# HELIALights2022V1_0Sheet2.net
KiCad netlist of a schematic drawn in Altium Designer
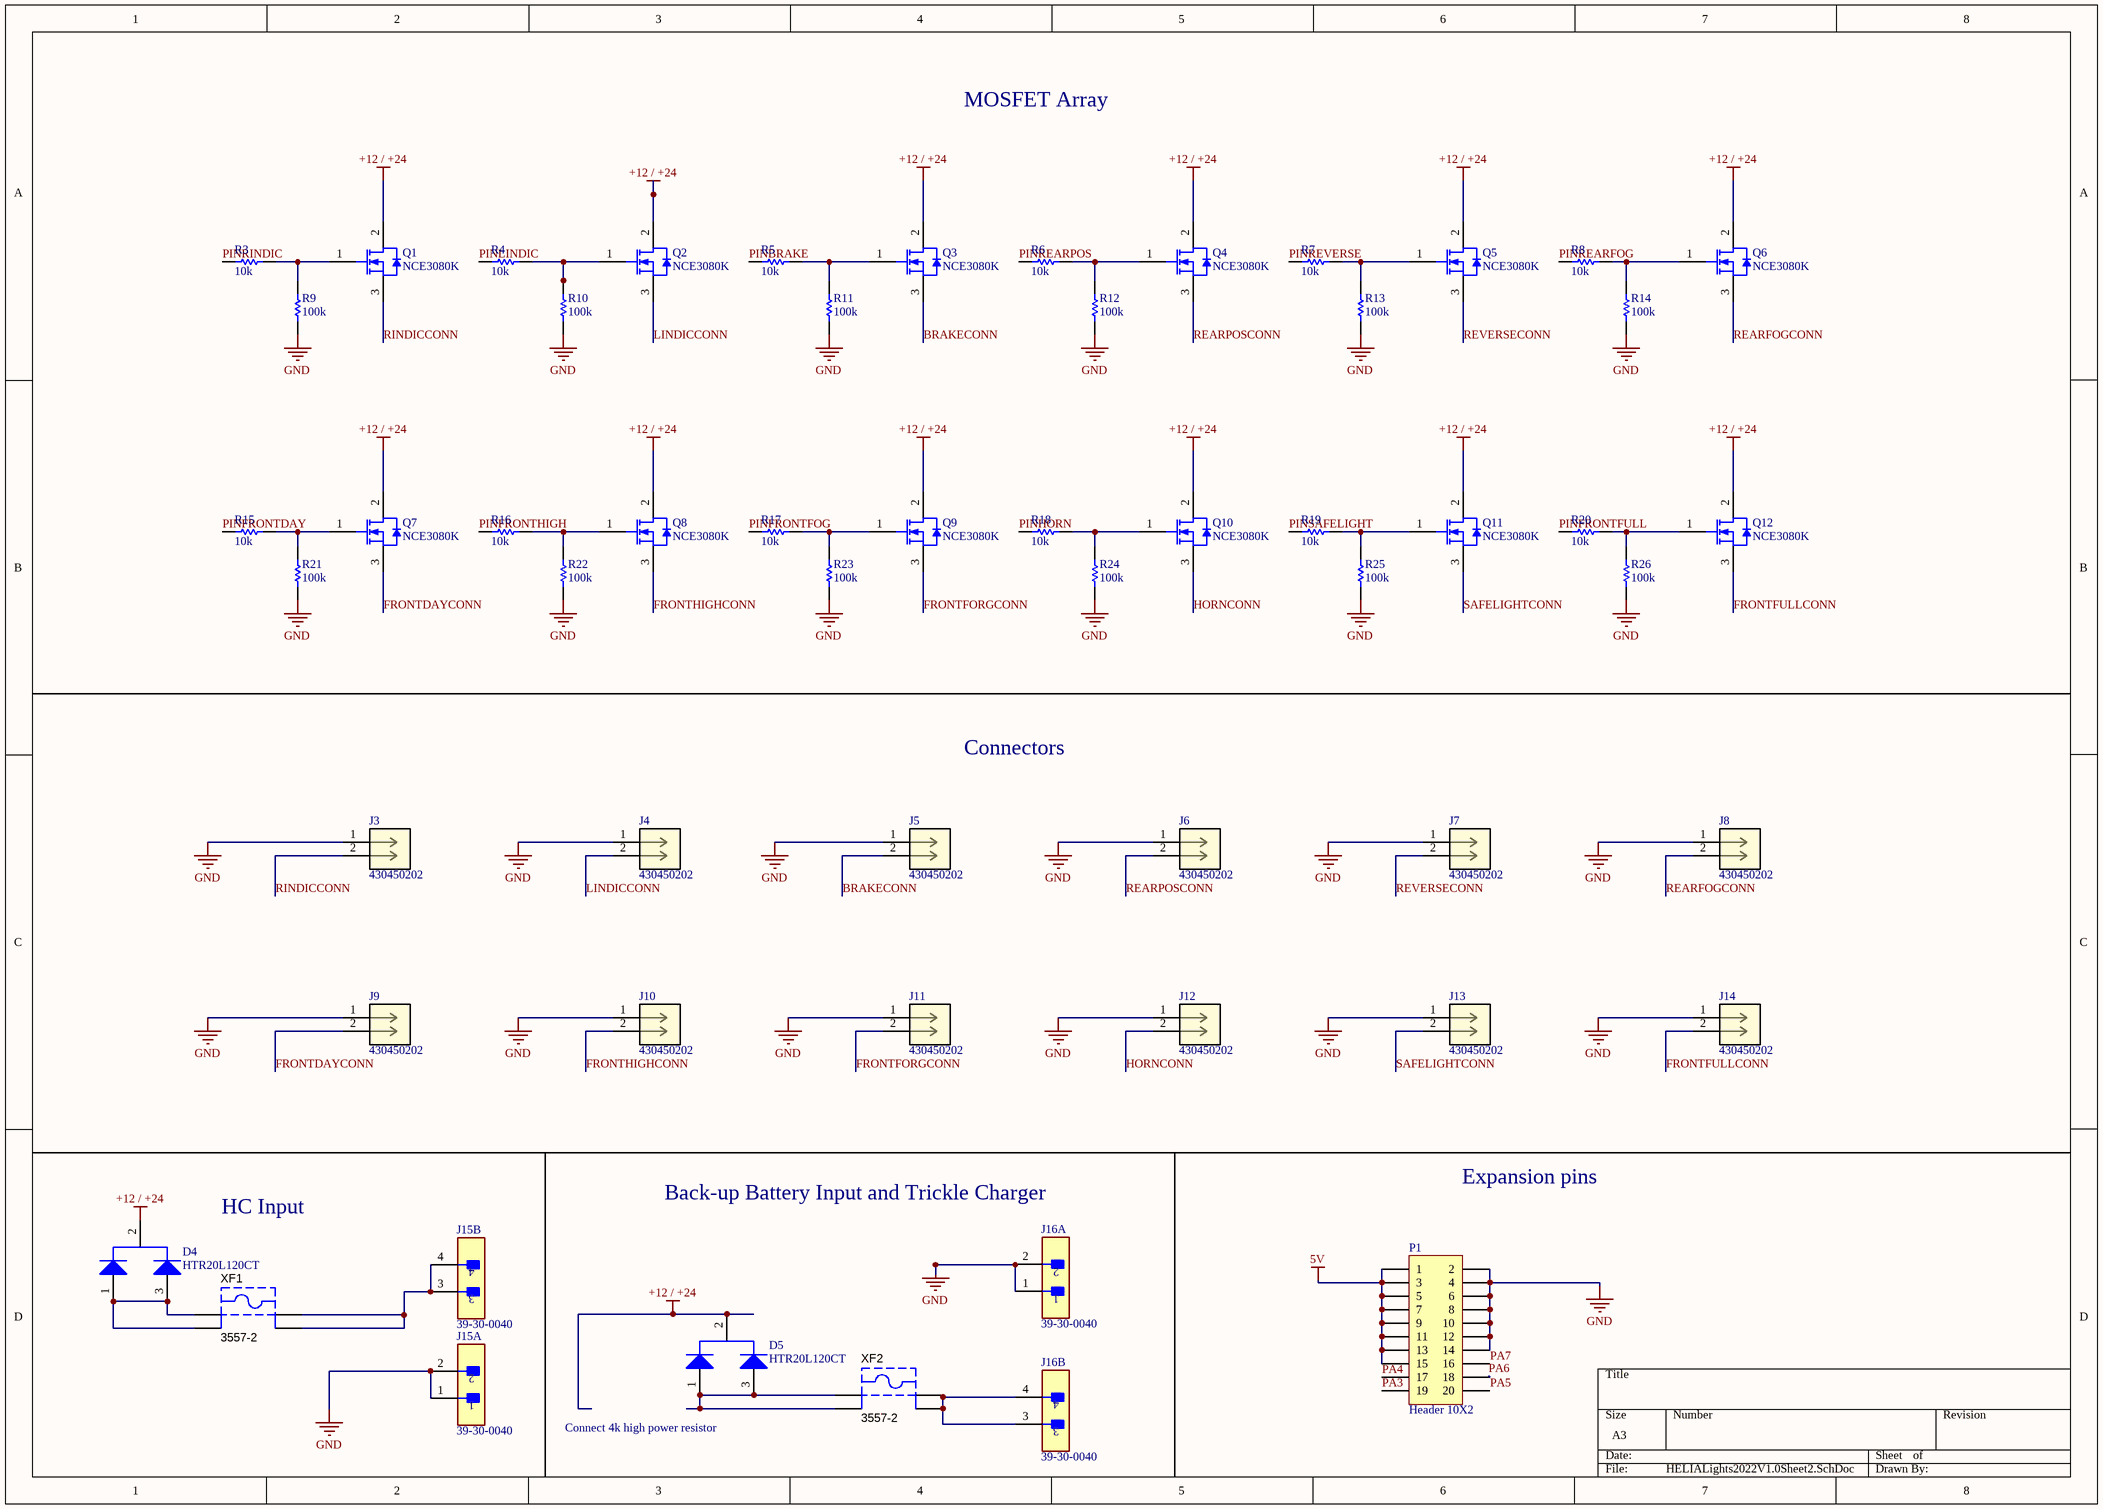
[diagram p0: HELIALights2022V1.0Sheet2.SchDoc]

(export (version "E")
  (design (tool "Eeschema 10.0.6"))
  (components
    (comp (ref "D4")
      (value "HTR20L120CT")
      (footprint "ONSC-TO-220-3-221A-09")
      (description "SWITCHMODE(TM) Power Rectifier, 60 V, 30 A, 3-Pin TO-220, Pb-Free, Tube")
      (fields (field (name "MANUFACTURER") "On Semiconductor") (field (name "PARTNUMBER") "MBR30H60CTG"))
      (libsource (lib "Altium Content Vault") (part "ONSC-D-A1K2A3-3_B"))
    )
    (comp (ref "D5")
      (value "HTR20L120CT")
      (footprint "ONSC-TO-220-3-221A-09")
      (description "SWITCHMODE(TM) Power Rectifier, 60 V, 30 A, 3-Pin TO-220, Pb-Free, Tube")
      (fields (field (name "MANUFACTURER") "On Semiconductor") (field (name "PARTNUMBER") "MBR30H60CTG"))
      (libsource (lib "Altium Content Vault") (part "ONSC-D-A1K2A3-3_B"))
    )
    (comp (ref "J3")
      (value "430450202")
      (footprint "CON_430450202_MOL")
      (description "No Description Available")
      (fields (field (name "COPYRIGHT") "Copyright (C) 2022 Ultra Librarian. All rights reserved."))
      (libsource (lib "430450202") (part "430450202"))
    )
    (comp (ref "J4")
      (value "430450202")
      (footprint "CON_430450202_MOL")
      (description "No Description Available")
      (fields (field (name "COPYRIGHT") "Copyright (C) 2022 Ultra Librarian. All rights reserved."))
      (libsource (lib "430450202") (part "430450202"))
    )
    (comp (ref "J5")
      (value "430450202")
      (footprint "CON_430450202_MOL")
      (description "No Description Available")
      (fields (field (name "COPYRIGHT") "Copyright (C) 2022 Ultra Librarian. All rights reserved."))
      (libsource (lib "430450202") (part "430450202"))
    )
    (comp (ref "J6")
      (value "430450202")
      (footprint "CON_430450202_MOL")
      (description "No Description Available")
      (fields (field (name "COPYRIGHT") "Copyright (C) 2022 Ultra Librarian. All rights reserved."))
      (libsource (lib "430450202") (part "430450202"))
    )
    (comp (ref "J7")
      (value "430450202")
      (footprint "CON_430450202_MOL")
      (description "No Description Available")
      (fields (field (name "COPYRIGHT") "Copyright (C) 2022 Ultra Librarian. All rights reserved."))
      (libsource (lib "430450202") (part "430450202"))
    )
    (comp (ref "J8")
      (value "430450202")
      (footprint "CON_430450202_MOL")
      (description "No Description Available")
      (fields (field (name "COPYRIGHT") "Copyright (C) 2022 Ultra Librarian. All rights reserved."))
      (libsource (lib "430450202") (part "430450202"))
    )
    (comp (ref "J9")
      (value "430450202")
      (footprint "CON_430450202_MOL")
      (description "No Description Available")
      (fields (field (name "COPYRIGHT") "Copyright (C) 2022 Ultra Librarian. All rights reserved."))
      (libsource (lib "430450202") (part "430450202"))
    )
    (comp (ref "J10")
      (value "430450202")
      (footprint "CON_430450202_MOL")
      (description "No Description Available")
      (fields (field (name "COPYRIGHT") "Copyright (C) 2022 Ultra Librarian. All rights reserved."))
      (libsource (lib "430450202") (part "430450202"))
    )
    (comp (ref "J11")
      (value "430450202")
      (footprint "CON_430450202_MOL")
      (description "No Description Available")
      (fields (field (name "COPYRIGHT") "Copyright (C) 2022 Ultra Librarian. All rights reserved."))
      (libsource (lib "430450202") (part "430450202"))
    )
    (comp (ref "J12")
      (value "430450202")
      (footprint "CON_430450202_MOL")
      (description "No Description Available")
      (fields (field (name "COPYRIGHT") "Copyright (C) 2022 Ultra Librarian. All rights reserved."))
      (libsource (lib "430450202") (part "430450202"))
    )
    (comp (ref "J13")
      (value "430450202")
      (footprint "CON_430450202_MOL")
      (description "No Description Available")
      (fields (field (name "COPYRIGHT") "Copyright (C) 2022 Ultra Librarian. All rights reserved."))
      (libsource (lib "430450202") (part "430450202"))
    )
    (comp (ref "J14")
      (value "430450202")
      (footprint "CON_430450202_MOL")
      (description "No Description Available")
      (fields (field (name "COPYRIGHT") "Copyright (C) 2022 Ultra Librarian. All rights reserved."))
      (libsource (lib "430450202") (part "430450202"))
    )
    (comp (ref "J15")
      (value "39-30-0040")
      (footprint "FP-39-30-0040-MFG")
      (description "CONN HEADER R/A 4POS 4.2MM")
      (fields
        (field (name "OCTOPART") "https://octopart.com/39-30-0040-molex-277428")
        (field (name "MANUFACTURER") "Molex")
      )
      (libsource (lib "Altium Content Vault") (part "ac72c5313ea981db199dbd0e8237b04"))
    )
    (comp (ref "J16")
      (value "39-30-0040")
      (footprint "FP-39-30-0040-MFG")
      (description "CONN HEADER R/A 4POS 4.2MM")
      (fields
        (field (name "OCTOPART") "https://octopart.com/39-30-0040-molex-277428")
        (field (name "MANUFACTURER") "Molex")
      )
      (libsource (lib "Altium Content Vault") (part "ac72c5313ea981db199dbd0e8237b04"))
    )
    (comp (ref "P1")
      (value "Header 10X2")
      (footprint "HDR2X10")
      (description "Header, 10-Pin, Dual row")
      (fields (field (name "PUBLISHER") "Altium Limited"))
      (libsource (lib "Miscellaneous Connectors") (part "Header 10X2"))
    )
    (comp (ref "Q1")
      (value "NCE3080K")
      (footprint "INF-PG-TO252-3-313_L")
      (fields (field (name "MANUFACTURER") "Infineon") (field (name "PARTNUMBER") "IPD60R600C6"))
      (libsource (lib "Altium Content Vault") (part "INF-NEMOS-GDS-3"))
    )
    (comp (ref "Q2")
      (value "NCE3080K")
      (footprint "INF-PG-TO252-3-313_L")
      (fields (field (name "MANUFACTURER") "Infineon") (field (name "PARTNUMBER") "IPD60R600C6"))
      (libsource (lib "Altium Content Vault") (part "INF-NEMOS-GDS-3"))
    )
    (comp (ref "Q3")
      (value "NCE3080K")
      (footprint "INF-PG-TO252-3-313_L")
      (fields (field (name "MANUFACTURER") "Infineon") (field (name "PARTNUMBER") "IPD60R600C6"))
      (libsource (lib "Altium Content Vault") (part "INF-NEMOS-GDS-3"))
    )
    (comp (ref "Q4")
      (value "NCE3080K")
      (footprint "INF-PG-TO252-3-313_L")
      (fields (field (name "MANUFACTURER") "Infineon") (field (name "PARTNUMBER") "IPD60R600C6"))
      (libsource (lib "Altium Content Vault") (part "INF-NEMOS-GDS-3"))
    )
    (comp (ref "Q5")
      (value "NCE3080K")
      (footprint "INF-PG-TO252-3-313_L")
      (fields (field (name "MANUFACTURER") "Infineon") (field (name "PARTNUMBER") "IPD60R600C6"))
      (libsource (lib "Altium Content Vault") (part "INF-NEMOS-GDS-3"))
    )
    (comp (ref "Q6")
      (value "NCE3080K")
      (footprint "INF-PG-TO252-3-313_L")
      (fields (field (name "MANUFACTURER") "Infineon") (field (name "PARTNUMBER") "IPD60R600C6"))
      (libsource (lib "Altium Content Vault") (part "INF-NEMOS-GDS-3"))
    )
    (comp (ref "Q7")
      (value "NCE3080K")
      (footprint "INF-PG-TO252-3-313_L")
      (fields (field (name "MANUFACTURER") "Infineon") (field (name "PARTNUMBER") "IPD60R600C6"))
      (libsource (lib "Altium Content Vault") (part "INF-NEMOS-GDS-3"))
    )
    (comp (ref "Q8")
      (value "NCE3080K")
      (footprint "INF-PG-TO252-3-313_L")
      (fields (field (name "MANUFACTURER") "Infineon") (field (name "PARTNUMBER") "IPD60R600C6"))
      (libsource (lib "Altium Content Vault") (part "INF-NEMOS-GDS-3"))
    )
    (comp (ref "Q9")
      (value "NCE3080K")
      (footprint "INF-PG-TO252-3-313_L")
      (fields (field (name "MANUFACTURER") "Infineon") (field (name "PARTNUMBER") "IPD60R600C6"))
      (libsource (lib "Altium Content Vault") (part "INF-NEMOS-GDS-3"))
    )
    (comp (ref "Q10")
      (value "NCE3080K")
      (footprint "INF-PG-TO252-3-313_L")
      (fields (field (name "MANUFACTURER") "Infineon") (field (name "PARTNUMBER") "IPD60R600C6"))
      (libsource (lib "Altium Content Vault") (part "INF-NEMOS-GDS-3"))
    )
    (comp (ref "Q11")
      (value "NCE3080K")
      (footprint "INF-PG-TO252-3-313_L")
      (fields (field (name "MANUFACTURER") "Infineon") (field (name "PARTNUMBER") "IPD60R600C6"))
      (libsource (lib "Altium Content Vault") (part "INF-NEMOS-GDS-3"))
    )
    (comp (ref "Q12")
      (value "NCE3080K")
      (footprint "INF-PG-TO252-3-313_L")
      (fields (field (name "MANUFACTURER") "Infineon") (field (name "PARTNUMBER") "IPD60R600C6"))
      (libsource (lib "Altium Content Vault") (part "INF-NEMOS-GDS-3"))
    )
    (comp (ref "R3")
      (value "10k")
      (footprint "RESC1609X50X30NL8T20")
      (description "Chip Resistor, 0 Ohm, Jumper, 100 mW, -55 to 155 degC, 0603 (1608 Metric), RoHS, Tape and Reel")
      (fields (field (name "MANUFACTURER") "Vishay Semiconductor"))
      (libsource (lib "Altium Content Vault") (part "RES-2"))
    )
    (comp (ref "R4")
      (value "10k")
      (footprint "RESC1609X50X30NL8T20")
      (description "Chip Resistor, 0 Ohm, Jumper, 100 mW, -55 to 155 degC, 0603 (1608 Metric), RoHS, Tape and Reel")
      (fields (field (name "MANUFACTURER") "Vishay Semiconductor"))
      (libsource (lib "Altium Content Vault") (part "RES-2"))
    )
    (comp (ref "R5")
      (value "10k")
      (footprint "RESC1609X50X30NL8T20")
      (description "Chip Resistor, 0 Ohm, Jumper, 100 mW, -55 to 155 degC, 0603 (1608 Metric), RoHS, Tape and Reel")
      (fields (field (name "MANUFACTURER") "Vishay Semiconductor"))
      (libsource (lib "Altium Content Vault") (part "RES-2"))
    )
    (comp (ref "R6")
      (value "10k")
      (footprint "RESC1609X50X30NL8T20")
      (description "Chip Resistor, 0 Ohm, Jumper, 100 mW, -55 to 155 degC, 0603 (1608 Metric), RoHS, Tape and Reel")
      (fields (field (name "MANUFACTURER") "Vishay Semiconductor"))
      (libsource (lib "Altium Content Vault") (part "RES-2"))
    )
    (comp (ref "R7")
      (value "10k")
      (footprint "RESC1609X50X30NL8T20")
      (description "Chip Resistor, 0 Ohm, Jumper, 100 mW, -55 to 155 degC, 0603 (1608 Metric), RoHS, Tape and Reel")
      (fields (field (name "MANUFACTURER") "Vishay Semiconductor"))
      (libsource (lib "Altium Content Vault") (part "RES-2"))
    )
    (comp (ref "R8")
      (value "10k")
      (footprint "RESC1609X50X30NL8T20")
      (description "Chip Resistor, 0 Ohm, Jumper, 100 mW, -55 to 155 degC, 0603 (1608 Metric), RoHS, Tape and Reel")
      (fields (field (name "MANUFACTURER") "Vishay Semiconductor"))
      (libsource (lib "Altium Content Vault") (part "RES-2"))
    )
    (comp (ref "R9")
      (value "100k")
      (footprint "RESC1609X50X30NL8T20")
      (description "Chip Resistor, 0 Ohm, Jumper, 100 mW, -55 to 155 degC, 0603 (1608 Metric), RoHS, Tape and Reel")
      (fields (field (name "MANUFACTURER") "Vishay Semiconductor"))
      (libsource (lib "Altium Content Vault") (part "RES-2"))
    )
    (comp (ref "R10")
      (value "100k")
      (footprint "RESC1609X50X30NL8T20")
      (description "Chip Resistor, 0 Ohm, Jumper, 100 mW, -55 to 155 degC, 0603 (1608 Metric), RoHS, Tape and Reel")
      (fields (field (name "MANUFACTURER") "Vishay Semiconductor"))
      (libsource (lib "Altium Content Vault") (part "RES-2"))
    )
    (comp (ref "R11")
      (value "100k")
      (footprint "RESC1609X50X30NL8T20")
      (description "Chip Resistor, 0 Ohm, Jumper, 100 mW, -55 to 155 degC, 0603 (1608 Metric), RoHS, Tape and Reel")
      (fields (field (name "MANUFACTURER") "Vishay Semiconductor"))
      (libsource (lib "Altium Content Vault") (part "RES-2"))
    )
    (comp (ref "R12")
      (value "100k")
      (footprint "RESC1609X50X30NL8T20")
      (description "Chip Resistor, 0 Ohm, Jumper, 100 mW, -55 to 155 degC, 0603 (1608 Metric), RoHS, Tape and Reel")
      (fields (field (name "MANUFACTURER") "Vishay Semiconductor"))
      (libsource (lib "Altium Content Vault") (part "RES-2"))
    )
    (comp (ref "R13")
      (value "100k")
      (footprint "RESC1609X50X30NL8T20")
      (description "Chip Resistor, 0 Ohm, Jumper, 100 mW, -55 to 155 degC, 0603 (1608 Metric), RoHS, Tape and Reel")
      (fields (field (name "MANUFACTURER") "Vishay Semiconductor"))
      (libsource (lib "Altium Content Vault") (part "RES-2"))
    )
    (comp (ref "R14")
      (value "100k")
      (footprint "RESC1609X50X30NL8T20")
      (description "Chip Resistor, 0 Ohm, Jumper, 100 mW, -55 to 155 degC, 0603 (1608 Metric), RoHS, Tape and Reel")
      (fields (field (name "MANUFACTURER") "Vishay Semiconductor"))
      (libsource (lib "Altium Content Vault") (part "RES-2"))
    )
    (comp (ref "R15")
      (value "10k")
      (footprint "RESC1609X50X30NL8T20")
      (description "Chip Resistor, 0 Ohm, Jumper, 100 mW, -55 to 155 degC, 0603 (1608 Metric), RoHS, Tape and Reel")
      (fields (field (name "MANUFACTURER") "Vishay Semiconductor"))
      (libsource (lib "Altium Content Vault") (part "RES-2"))
    )
    (comp (ref "R16")
      (value "10k")
      (footprint "RESC1609X50X30NL8T20")
      (description "Chip Resistor, 0 Ohm, Jumper, 100 mW, -55 to 155 degC, 0603 (1608 Metric), RoHS, Tape and Reel")
      (fields (field (name "MANUFACTURER") "Vishay Semiconductor"))
      (libsource (lib "Altium Content Vault") (part "RES-2"))
    )
    (comp (ref "R17")
      (value "10k")
      (footprint "RESC1609X50X30NL8T20")
      (description "Chip Resistor, 0 Ohm, Jumper, 100 mW, -55 to 155 degC, 0603 (1608 Metric), RoHS, Tape and Reel")
      (fields (field (name "MANUFACTURER") "Vishay Semiconductor"))
      (libsource (lib "Altium Content Vault") (part "RES-2"))
    )
    (comp (ref "R18")
      (value "10k")
      (footprint "RESC1609X50X30NL8T20")
      (description "Chip Resistor, 0 Ohm, Jumper, 100 mW, -55 to 155 degC, 0603 (1608 Metric), RoHS, Tape and Reel")
      (fields (field (name "MANUFACTURER") "Vishay Semiconductor"))
      (libsource (lib "Altium Content Vault") (part "RES-2"))
    )
    (comp (ref "R19")
      (value "10k")
      (footprint "RESC1609X50X30NL8T20")
      (description "Chip Resistor, 0 Ohm, Jumper, 100 mW, -55 to 155 degC, 0603 (1608 Metric), RoHS, Tape and Reel")
      (fields (field (name "MANUFACTURER") "Vishay Semiconductor"))
      (libsource (lib "Altium Content Vault") (part "RES-2"))
    )
    (comp (ref "R20")
      (value "10k")
      (footprint "RESC1609X50X30NL8T20")
      (description "Chip Resistor, 0 Ohm, Jumper, 100 mW, -55 to 155 degC, 0603 (1608 Metric), RoHS, Tape and Reel")
      (fields (field (name "MANUFACTURER") "Vishay Semiconductor"))
      (libsource (lib "Altium Content Vault") (part "RES-2"))
    )
    (comp (ref "R21")
      (value "100k")
      (footprint "RESC1609X50X30NL8T20")
      (description "Chip Resistor, 0 Ohm, Jumper, 100 mW, -55 to 155 degC, 0603 (1608 Metric), RoHS, Tape and Reel")
      (fields (field (name "MANUFACTURER") "Vishay Semiconductor"))
      (libsource (lib "Altium Content Vault") (part "RES-2"))
    )
    (comp (ref "R22")
      (value "100k")
      (footprint "RESC1609X50X30NL8T20")
      (description "Chip Resistor, 0 Ohm, Jumper, 100 mW, -55 to 155 degC, 0603 (1608 Metric), RoHS, Tape and Reel")
      (fields (field (name "MANUFACTURER") "Vishay Semiconductor"))
      (libsource (lib "Altium Content Vault") (part "RES-2"))
    )
    (comp (ref "R23")
      (value "100k")
      (footprint "RESC1609X50X30NL8T20")
      (description "Chip Resistor, 0 Ohm, Jumper, 100 mW, -55 to 155 degC, 0603 (1608 Metric), RoHS, Tape and Reel")
      (fields (field (name "MANUFACTURER") "Vishay Semiconductor"))
      (libsource (lib "Altium Content Vault") (part "RES-2"))
    )
    (comp (ref "R24")
      (value "100k")
      (footprint "RESC1609X50X30NL8T20")
      (description "Chip Resistor, 0 Ohm, Jumper, 100 mW, -55 to 155 degC, 0603 (1608 Metric), RoHS, Tape and Reel")
      (fields (field (name "MANUFACTURER") "Vishay Semiconductor"))
      (libsource (lib "Altium Content Vault") (part "RES-2"))
    )
    (comp (ref "R25")
      (value "100k")
      (footprint "RESC1609X50X30NL8T20")
      (description "Chip Resistor, 0 Ohm, Jumper, 100 mW, -55 to 155 degC, 0603 (1608 Metric), RoHS, Tape and Reel")
      (fields (field (name "MANUFACTURER") "Vishay Semiconductor"))
      (libsource (lib "Altium Content Vault") (part "RES-2"))
    )
    (comp (ref "R26")
      (value "100k")
      (footprint "RESC1609X50X30NL8T20")
      (description "Chip Resistor, 0 Ohm, Jumper, 100 mW, -55 to 155 degC, 0603 (1608 Metric), RoHS, Tape and Reel")
      (fields (field (name "MANUFACTURER") "Vishay Semiconductor"))
      (libsource (lib "Altium Content Vault") (part "RES-2"))
    )
    (comp (ref "XF1")
      (value "3557-2")
      (footprint "KSTN-3557-2")
      (description "FUSE HOLDER, PCB MOUNT, 500VAC, 20A, ROHS")
      (fields (field (name "VOLTAGE") "500V") (field (name "MANUFACTURER") "Keystone-Electronics"))
      (libsource (lib "Altium Content Vault") (part "FUSE_HOLDER-4"))
    )
    (comp (ref "XF2")
      (value "3557-2")
      (footprint "KSTN-3557-2")
      (description "FUSE HOLDER, PCB MOUNT, 500VAC, 20A, ROHS")
      (fields (field (name "VOLTAGE") "500V") (field (name "MANUFACTURER") "Keystone-Electronics"))
      (libsource (lib "Altium Content Vault") (part "FUSE_HOLDER-4"))
    )
  )
  (nets
    (net (code "1") (name "+12 {slash} +24") (class "Default")
      (node (ref "D4") (pin "2") (pinfunction "K_2") (pintype "passive"))
      (node (ref "D5") (pin "2") (pinfunction "K_2") (pintype "passive"))
      (node (ref "Q1") (pin "2") (pinfunction "DRAIN_2") (pintype "passive"))
      (node (ref "Q10") (pin "2") (pinfunction "DRAIN_2") (pintype "passive"))
      (node (ref "Q11") (pin "2") (pinfunction "DRAIN_2") (pintype "passive"))
      (node (ref "Q12") (pin "2") (pinfunction "DRAIN_2") (pintype "passive"))
      (node (ref "Q2") (pin "2") (pinfunction "DRAIN_2") (pintype "passive"))
      (node (ref "Q3") (pin "2") (pinfunction "DRAIN_2") (pintype "passive"))
      (node (ref "Q4") (pin "2") (pinfunction "DRAIN_2") (pintype "passive"))
      (node (ref "Q5") (pin "2") (pinfunction "DRAIN_2") (pintype "passive"))
      (node (ref "Q6") (pin "2") (pinfunction "DRAIN_2") (pintype "passive"))
      (node (ref "Q7") (pin "2") (pinfunction "DRAIN_2") (pintype "passive"))
      (node (ref "Q8") (pin "2") (pinfunction "DRAIN_2") (pintype "passive"))
      (node (ref "Q9") (pin "2") (pinfunction "DRAIN_2") (pintype "passive"))
    )
    (net (code "2") (name "/BRAKECONN") (class "Default")
      (node (ref "J5") (pin "2") (pinfunction "2_2") (pintype "passive"))
      (node (ref "Q3") (pin "3") (pinfunction "SOURCE_3") (pintype "passive"))
    )
    (net (code "3") (name "/FRONTDAYCONN") (class "Default")
      (node (ref "J9") (pin "2") (pinfunction "2_2") (pintype "passive"))
      (node (ref "Q7") (pin "3") (pinfunction "SOURCE_3") (pintype "passive"))
    )
    (net (code "4") (name "/FRONTFORGCONN") (class "Default")
      (node (ref "J11") (pin "2") (pinfunction "2_2") (pintype "passive"))
      (node (ref "Q9") (pin "3") (pinfunction "SOURCE_3") (pintype "passive"))
    )
    (net (code "5") (name "/FRONTFULLCONN") (class "Default")
      (node (ref "J14") (pin "2") (pinfunction "2_2") (pintype "passive"))
      (node (ref "Q12") (pin "3") (pinfunction "SOURCE_3") (pintype "passive"))
    )
    (net (code "6") (name "/FRONTHIGHCONN") (class "Default")
      (node (ref "J10") (pin "2") (pinfunction "2_2") (pintype "passive"))
      (node (ref "Q8") (pin "3") (pinfunction "SOURCE_3") (pintype "passive"))
    )
    (net (code "7") (name "/HORNCONN") (class "Default")
      (node (ref "J12") (pin "2") (pinfunction "2_2") (pintype "passive"))
      (node (ref "Q10") (pin "3") (pinfunction "SOURCE_3") (pintype "passive"))
    )
    (net (code "8") (name "/LINDICCONN") (class "Default")
      (node (ref "J4") (pin "2") (pinfunction "2_2") (pintype "passive"))
      (node (ref "Q2") (pin "3") (pinfunction "SOURCE_3") (pintype "passive"))
    )
    (net (code "9") (name "/PA3") (class "Default")
      (node (ref "P1") (pin "19") (pinfunction "19_19") (pintype "passive"))
    )
    (net (code "10") (name "/PA4") (class "Default")
      (node (ref "P1") (pin "17") (pinfunction "17_17") (pintype "passive"))
    )
    (net (code "11") (name "/PA5") (class "Default")
      (node (ref "P1") (pin "20") (pinfunction "20_20") (pintype "passive"))
    )
    (net (code "12") (name "/PA6") (class "Default")
      (node (ref "P1") (pin "18") (pinfunction "18_18") (pintype "passive"))
    )
    (net (code "13") (name "/PA7") (class "Default")
      (node (ref "P1") (pin "16") (pinfunction "16_16") (pintype "passive"))
    )
    (net (code "14") (name "/PINBRAKE") (class "Default")
      (node (ref "R5") (pin "2") (pinfunction "2_2") (pintype "passive"))
    )
    (net (code "15") (name "/PINFRONTDAY") (class "Default")
      (node (ref "R15") (pin "2") (pinfunction "2_2") (pintype "passive"))
    )
    (net (code "16") (name "/PINFRONTFOG") (class "Default")
      (node (ref "R17") (pin "2") (pinfunction "2_2") (pintype "passive"))
    )
    (net (code "17") (name "/PINFRONTFULL") (class "Default")
      (node (ref "R20") (pin "2") (pinfunction "2_2") (pintype "passive"))
    )
    (net (code "18") (name "/PINFRONTHIGH") (class "Default")
      (node (ref "R16") (pin "2") (pinfunction "2_2") (pintype "passive"))
    )
    (net (code "19") (name "/PINHORN") (class "Default")
      (node (ref "R18") (pin "2") (pinfunction "2_2") (pintype "passive"))
    )
    (net (code "20") (name "/PINLINDIC") (class "Default")
      (node (ref "R4") (pin "2") (pinfunction "2_2") (pintype "passive"))
    )
    (net (code "21") (name "/PINREARFOG") (class "Default")
      (node (ref "R8") (pin "2") (pinfunction "2_2") (pintype "passive"))
    )
    (net (code "22") (name "/PINREARPOS") (class "Default")
      (node (ref "R6") (pin "2") (pinfunction "2_2") (pintype "passive"))
    )
    (net (code "23") (name "/PINREVERSE") (class "Default")
      (node (ref "R7") (pin "2") (pinfunction "2_2") (pintype "passive"))
    )
    (net (code "24") (name "/PINRINDIC") (class "Default")
      (node (ref "R3") (pin "2") (pinfunction "2_2") (pintype "passive"))
    )
    (net (code "25") (name "/PINSAFELIGHT") (class "Default")
      (node (ref "R19") (pin "2") (pinfunction "2_2") (pintype "passive"))
    )
    (net (code "26") (name "/REARFOGCONN") (class "Default")
      (node (ref "J8") (pin "2") (pinfunction "2_2") (pintype "passive"))
      (node (ref "Q6") (pin "3") (pinfunction "SOURCE_3") (pintype "passive"))
    )
    (net (code "27") (name "/REARPOSCONN") (class "Default")
      (node (ref "J6") (pin "2") (pinfunction "2_2") (pintype "passive"))
      (node (ref "Q4") (pin "3") (pinfunction "SOURCE_3") (pintype "passive"))
    )
    (net (code "28") (name "/REVERSECONN") (class "Default")
      (node (ref "J7") (pin "2") (pinfunction "2_2") (pintype "passive"))
      (node (ref "Q5") (pin "3") (pinfunction "SOURCE_3") (pintype "passive"))
    )
    (net (code "29") (name "/RINDICCONN") (class "Default")
      (node (ref "J3") (pin "2") (pinfunction "2_2") (pintype "passive"))
      (node (ref "Q1") (pin "3") (pinfunction "SOURCE_3") (pintype "passive"))
    )
    (net (code "30") (name "/SAFELIGHTCONN") (class "Default")
      (node (ref "J13") (pin "2") (pinfunction "2_2") (pintype "passive"))
      (node (ref "Q11") (pin "3") (pinfunction "SOURCE_3") (pintype "passive"))
    )
    (net (code "31") (name "5V") (class "Default")
      (node (ref "P1") (pin "1") (pinfunction "1_1") (pintype "passive"))
      (node (ref "P1") (pin "11") (pinfunction "11_11") (pintype "passive"))
      (node (ref "P1") (pin "13") (pinfunction "13_13") (pintype "passive"))
      (node (ref "P1") (pin "15") (pinfunction "15_15") (pintype "passive"))
      (node (ref "P1") (pin "3") (pinfunction "3_3") (pintype "passive"))
      (node (ref "P1") (pin "5") (pinfunction "5_5") (pintype "passive"))
      (node (ref "P1") (pin "7") (pinfunction "7_7") (pintype "passive"))
      (node (ref "P1") (pin "9") (pinfunction "9_9") (pintype "passive"))
    )
    (net (code "32") (name "GND") (class "Default")
      (node (ref "J10") (pin "1") (pinfunction "1_1") (pintype "passive"))
      (node (ref "J11") (pin "1") (pinfunction "1_1") (pintype "passive"))
      (node (ref "J12") (pin "1") (pinfunction "1_1") (pintype "passive"))
      (node (ref "J13") (pin "1") (pinfunction "1_1") (pintype "passive"))
      (node (ref "J14") (pin "1") (pinfunction "1_1") (pintype "passive"))
      (node (ref "J15") (pin "1") (pinfunction "1_1") (pintype "passive"))
      (node (ref "J15") (pin "2") (pinfunction "2_2") (pintype "passive"))
      (node (ref "J16") (pin "1") (pinfunction "1_1") (pintype "passive"))
      (node (ref "J16") (pin "2") (pinfunction "2_2") (pintype "passive"))
      (node (ref "J3") (pin "1") (pinfunction "1_1") (pintype "passive"))
      (node (ref "J4") (pin "1") (pinfunction "1_1") (pintype "passive"))
      (node (ref "J5") (pin "1") (pinfunction "1_1") (pintype "passive"))
      (node (ref "J6") (pin "1") (pinfunction "1_1") (pintype "passive"))
      (node (ref "J7") (pin "1") (pinfunction "1_1") (pintype "passive"))
      (node (ref "J8") (pin "1") (pinfunction "1_1") (pintype "passive"))
      (node (ref "J9") (pin "1") (pinfunction "1_1") (pintype "passive"))
      (node (ref "P1") (pin "10") (pinfunction "10_10") (pintype "passive"))
      (node (ref "P1") (pin "12") (pinfunction "12_12") (pintype "passive"))
      (node (ref "P1") (pin "14") (pinfunction "14_14") (pintype "passive"))
      (node (ref "P1") (pin "2") (pinfunction "2_2") (pintype "passive"))
      (node (ref "P1") (pin "4") (pinfunction "4_4") (pintype "passive"))
      (node (ref "P1") (pin "6") (pinfunction "6_6") (pintype "passive"))
      (node (ref "P1") (pin "8") (pinfunction "8_8") (pintype "passive"))
      (node (ref "R10") (pin "2") (pinfunction "2_2") (pintype "passive"))
      (node (ref "R11") (pin "2") (pinfunction "2_2") (pintype "passive"))
      (node (ref "R12") (pin "2") (pinfunction "2_2") (pintype "passive"))
      (node (ref "R13") (pin "2") (pinfunction "2_2") (pintype "passive"))
      (node (ref "R14") (pin "2") (pinfunction "2_2") (pintype "passive"))
      (node (ref "R21") (pin "2") (pinfunction "2_2") (pintype "passive"))
      (node (ref "R22") (pin "2") (pinfunction "2_2") (pintype "passive"))
      (node (ref "R23") (pin "2") (pinfunction "2_2") (pintype "passive"))
      (node (ref "R24") (pin "2") (pinfunction "2_2") (pintype "passive"))
      (node (ref "R25") (pin "2") (pinfunction "2_2") (pintype "passive"))
      (node (ref "R26") (pin "2") (pinfunction "2_2") (pintype "passive"))
      (node (ref "R9") (pin "2") (pinfunction "2_2") (pintype "passive"))
    )
    (net (code "33") (name "Net-(D4-A1)") (class "Default")
      (node (ref "D4") (pin "1") (pinfunction "A1_1") (pintype "passive"))
      (node (ref "D4") (pin "3") (pinfunction "A2_3") (pintype "passive"))
      (node (ref "XF1") (pin "1") (pinfunction "1_1") (pintype "passive"))
      (node (ref "XF1") (pin "2") (pinfunction "2_2") (pintype "passive"))
    )
    (net (code "34") (name "Net-(D5-A1)") (class "Default")
      (node (ref "D5") (pin "1") (pinfunction "A1_1") (pintype "passive"))
      (node (ref "D5") (pin "3") (pinfunction "A2_3") (pintype "passive"))
      (node (ref "XF2") (pin "1") (pinfunction "1_1") (pintype "passive"))
      (node (ref "XF2") (pin "2") (pinfunction "2_2") (pintype "passive"))
    )
    (net (code "35") (name "Net-(J15-Pad3)") (class "Default")
      (node (ref "J15") (pin "3") (pinfunction "3_3") (pintype "passive"))
      (node (ref "J15") (pin "4") (pinfunction "4_4") (pintype "passive"))
      (node (ref "XF1") (pin "3") (pinfunction "3_3") (pintype "passive"))
      (node (ref "XF1") (pin "4") (pinfunction "4_4") (pintype "passive"))
    )
    (net (code "36") (name "Net-(J16-Pad3)") (class "Default")
      (node (ref "J16") (pin "3") (pinfunction "3_3") (pintype "passive"))
      (node (ref "J16") (pin "4") (pinfunction "4_4") (pintype "passive"))
      (node (ref "XF2") (pin "3") (pinfunction "3_3") (pintype "passive"))
      (node (ref "XF2") (pin "4") (pinfunction "4_4") (pintype "passive"))
    )
    (net (code "37") (name "Net-(Q1-GATE)") (class "Default")
      (node (ref "Q1") (pin "1") (pinfunction "GATE_1") (pintype "passive"))
      (node (ref "R3") (pin "1") (pinfunction "1_1") (pintype "passive"))
      (node (ref "R9") (pin "1") (pinfunction "1_1") (pintype "passive"))
    )
    (net (code "38") (name "Net-(Q2-GATE)") (class "Default")
      (node (ref "Q2") (pin "1") (pinfunction "GATE_1") (pintype "passive"))
      (node (ref "R10") (pin "1") (pinfunction "1_1") (pintype "passive"))
      (node (ref "R4") (pin "1") (pinfunction "1_1") (pintype "passive"))
    )
    (net (code "39") (name "Net-(Q3-GATE)") (class "Default")
      (node (ref "Q3") (pin "1") (pinfunction "GATE_1") (pintype "passive"))
      (node (ref "R11") (pin "1") (pinfunction "1_1") (pintype "passive"))
      (node (ref "R5") (pin "1") (pinfunction "1_1") (pintype "passive"))
    )
    (net (code "40") (name "Net-(Q4-GATE)") (class "Default")
      (node (ref "Q4") (pin "1") (pinfunction "GATE_1") (pintype "passive"))
      (node (ref "R12") (pin "1") (pinfunction "1_1") (pintype "passive"))
      (node (ref "R6") (pin "1") (pinfunction "1_1") (pintype "passive"))
    )
    (net (code "41") (name "Net-(Q5-GATE)") (class "Default")
      (node (ref "Q5") (pin "1") (pinfunction "GATE_1") (pintype "passive"))
      (node (ref "R13") (pin "1") (pinfunction "1_1") (pintype "passive"))
      (node (ref "R7") (pin "1") (pinfunction "1_1") (pintype "passive"))
    )
    (net (code "42") (name "Net-(Q6-GATE)") (class "Default")
      (node (ref "Q6") (pin "1") (pinfunction "GATE_1") (pintype "passive"))
      (node (ref "R14") (pin "1") (pinfunction "1_1") (pintype "passive"))
      (node (ref "R8") (pin "1") (pinfunction "1_1") (pintype "passive"))
    )
    (net (code "43") (name "Net-(Q7-GATE)") (class "Default")
      (node (ref "Q7") (pin "1") (pinfunction "GATE_1") (pintype "passive"))
      (node (ref "R15") (pin "1") (pinfunction "1_1") (pintype "passive"))
      (node (ref "R21") (pin "1") (pinfunction "1_1") (pintype "passive"))
    )
    (net (code "44") (name "Net-(Q8-GATE)") (class "Default")
      (node (ref "Q8") (pin "1") (pinfunction "GATE_1") (pintype "passive"))
      (node (ref "R16") (pin "1") (pinfunction "1_1") (pintype "passive"))
      (node (ref "R22") (pin "1") (pinfunction "1_1") (pintype "passive"))
    )
    (net (code "45") (name "Net-(Q9-GATE)") (class "Default")
      (node (ref "Q9") (pin "1") (pinfunction "GATE_1") (pintype "passive"))
      (node (ref "R17") (pin "1") (pinfunction "1_1") (pintype "passive"))
      (node (ref "R23") (pin "1") (pinfunction "1_1") (pintype "passive"))
    )
    (net (code "46") (name "Net-(Q10-GATE)") (class "Default")
      (node (ref "Q10") (pin "1") (pinfunction "GATE_1") (pintype "passive"))
      (node (ref "R18") (pin "1") (pinfunction "1_1") (pintype "passive"))
      (node (ref "R24") (pin "1") (pinfunction "1_1") (pintype "passive"))
    )
    (net (code "47") (name "Net-(Q11-GATE)") (class "Default")
      (node (ref "Q11") (pin "1") (pinfunction "GATE_1") (pintype "passive"))
      (node (ref "R19") (pin "1") (pinfunction "1_1") (pintype "passive"))
      (node (ref "R25") (pin "1") (pinfunction "1_1") (pintype "passive"))
    )
    (net (code "48") (name "Net-(Q12-GATE)") (class "Default")
      (node (ref "Q12") (pin "1") (pinfunction "GATE_1") (pintype "passive"))
      (node (ref "R20") (pin "1") (pinfunction "1_1") (pintype "passive"))
      (node (ref "R26") (pin "1") (pinfunction "1_1") (pintype "passive"))
    )
  )
)
